# Sheet1.net
KiCad netlist of a schematic drawn in Altium Designer
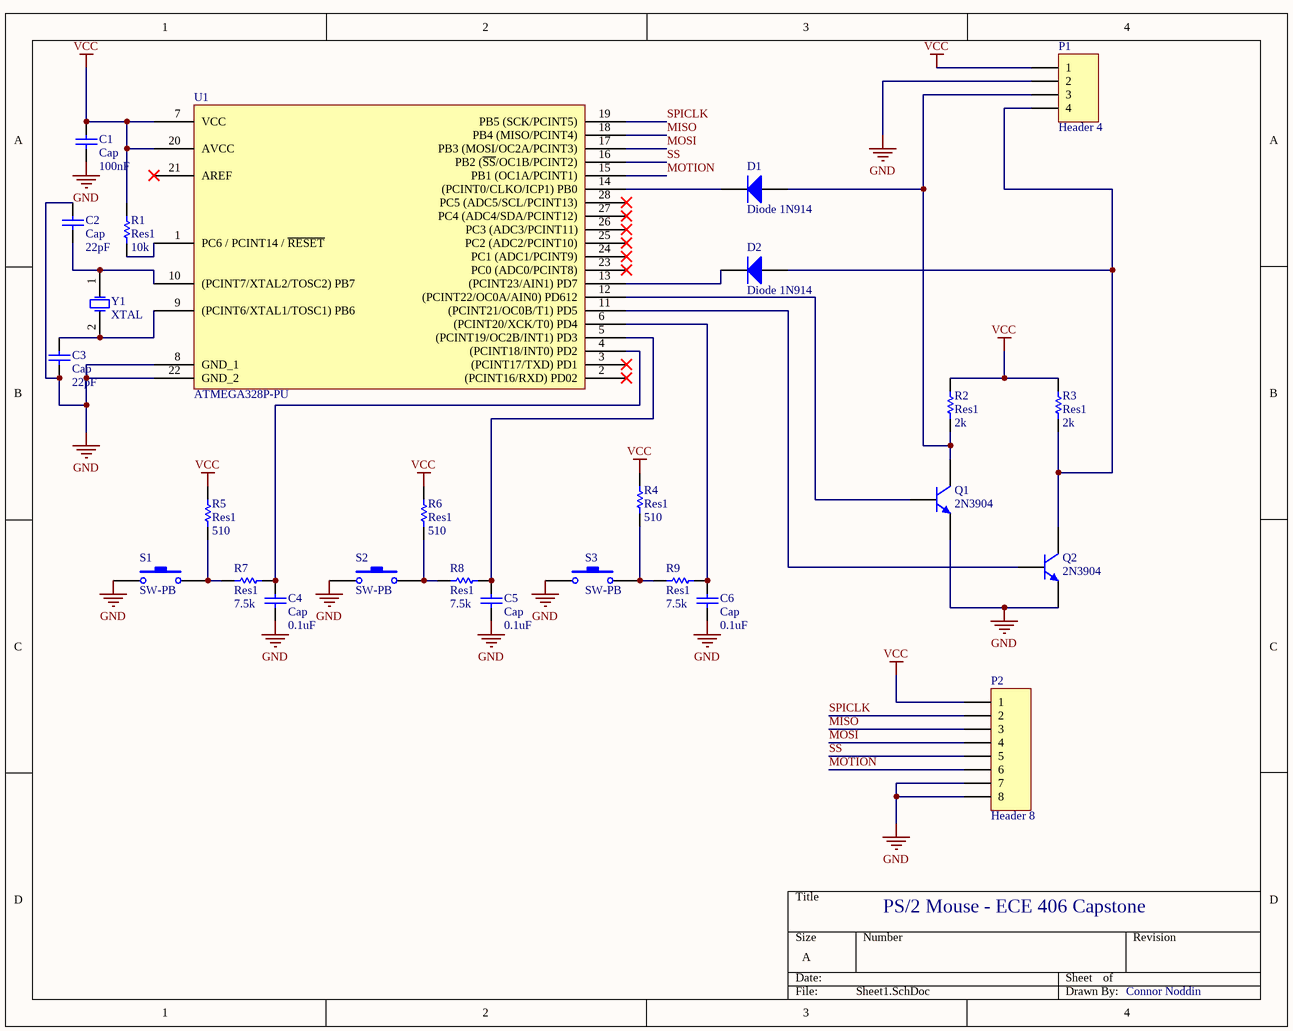
[diagram p0: Sheet1.SchDoc]

(export (version "E")
  (design (tool "Eeschema 10.0.6"))
  (components
    (comp (ref "C1")
      (value "Cap")
      (footprint "RAD-0.3")
      (description "Capacitor")
      (fields (field (name "ALTIUM_VALUE") "100nF") (field (name "PUBLISHER") "Altium Limited"))
      (libsource (lib "Miscellaneous Devices") (part "Cap"))
    )
    (comp (ref "C2")
      (value "Cap")
      (footprint "RAD-0.3")
      (description "Capacitor")
      (fields (field (name "ALTIUM_VALUE") "22pF") (field (name "PUBLISHER") "Altium Limited"))
      (libsource (lib "Miscellaneous Devices") (part "Cap"))
    )
    (comp (ref "C3")
      (value "Cap")
      (footprint "RAD-0.3")
      (description "Capacitor")
      (fields (field (name "ALTIUM_VALUE") "22pF") (field (name "PUBLISHER") "Altium Limited"))
      (libsource (lib "Miscellaneous Devices") (part "Cap"))
    )
    (comp (ref "C4")
      (value "Cap")
      (footprint "RAD-0.3")
      (description "Capacitor")
      (fields (field (name "ALTIUM_VALUE") "0.1uF") (field (name "PUBLISHER") "Altium Limited"))
      (libsource (lib "Miscellaneous Devices") (part "Cap"))
    )
    (comp (ref "C5")
      (value "Cap")
      (footprint "RAD-0.3")
      (description "Capacitor")
      (fields (field (name "ALTIUM_VALUE") "0.1uF") (field (name "PUBLISHER") "Altium Limited"))
      (libsource (lib "Miscellaneous Devices") (part "Cap"))
    )
    (comp (ref "C6")
      (value "Cap")
      (footprint "RAD-0.3")
      (description "Capacitor")
      (fields (field (name "ALTIUM_VALUE") "0.1uF") (field (name "PUBLISHER") "Altium Limited"))
      (libsource (lib "Miscellaneous Devices") (part "Cap"))
    )
    (comp (ref "D1")
      (value "Diode 1N914")
      (footprint "DO-35")
      (description "High Conductance Fast Diode")
      (fields (field (name "PUBLISHER") "Altium Limited"))
      (libsource (lib "Miscellaneous Devices") (part "Diode 1N914"))
    )
    (comp (ref "D2")
      (value "Diode 1N914")
      (footprint "DO-35")
      (description "High Conductance Fast Diode")
      (fields (field (name "PUBLISHER") "Altium Limited"))
      (libsource (lib "Miscellaneous Devices") (part "Diode 1N914"))
    )
    (comp (ref "P1")
      (value "Header 4")
      (footprint "HDR1X4")
      (description "Header, 4-Pin")
      (fields (field (name "PUBLISHER") "Altium Limited"))
      (libsource (lib "Miscellaneous Connectors") (part "Header 4"))
    )
    (comp (ref "P2")
      (value "Header 8")
      (footprint "HDR1X8")
      (description "Header, 8-Pin")
      (fields (field (name "PUBLISHER") "Altium Limited"))
      (libsource (lib "Miscellaneous Connectors") (part "Header 8"))
    )
    (comp (ref "Q1")
      (value "2N3904")
      (footprint "TO-92A")
      (description "NPN General Purpose Amplifier")
      (fields (field (name "PUBLISHER") "Altium Limited"))
      (libsource (lib "Miscellaneous Devices") (part "2N3904"))
    )
    (comp (ref "Q2")
      (value "2N3904")
      (footprint "TO-92A")
      (description "NPN General Purpose Amplifier")
      (fields (field (name "PUBLISHER") "Altium Limited"))
      (libsource (lib "Miscellaneous Devices") (part "2N3904"))
    )
    (comp (ref "R1")
      (value "Res1")
      (footprint "AXIAL-0.3")
      (description "Resistor")
      (fields (field (name "ALTIUM_VALUE") "10k") (field (name "PUBLISHER") "Altium Limited"))
      (libsource (lib "Miscellaneous Devices") (part "Res1"))
    )
    (comp (ref "R2")
      (value "Res1")
      (footprint "AXIAL-0.3")
      (description "Resistor")
      (fields (field (name "ALTIUM_VALUE") "2k") (field (name "PUBLISHER") "Altium Limited"))
      (libsource (lib "Miscellaneous Devices") (part "Res1"))
    )
    (comp (ref "R3")
      (value "Res1")
      (footprint "AXIAL-0.3")
      (description "Resistor")
      (fields (field (name "ALTIUM_VALUE") "2k") (field (name "PUBLISHER") "Altium Limited"))
      (libsource (lib "Miscellaneous Devices") (part "Res1"))
    )
    (comp (ref "R4")
      (value "Res1")
      (footprint "AXIAL-0.3")
      (description "Resistor")
      (fields (field (name "ALTIUM_VALUE") "510") (field (name "PUBLISHER") "Altium Limited"))
      (libsource (lib "Miscellaneous Devices") (part "Res1"))
    )
    (comp (ref "R5")
      (value "Res1")
      (footprint "AXIAL-0.3")
      (description "Resistor")
      (fields (field (name "ALTIUM_VALUE") "510") (field (name "PUBLISHER") "Altium Limited"))
      (libsource (lib "Miscellaneous Devices") (part "Res1"))
    )
    (comp (ref "R6")
      (value "Res1")
      (footprint "AXIAL-0.3")
      (description "Resistor")
      (fields (field (name "ALTIUM_VALUE") "510") (field (name "PUBLISHER") "Altium Limited"))
      (libsource (lib "Miscellaneous Devices") (part "Res1"))
    )
    (comp (ref "R7")
      (value "Res1")
      (footprint "AXIAL-0.3")
      (description "Resistor")
      (fields (field (name "ALTIUM_VALUE") "7.5k") (field (name "PUBLISHER") "Altium Limited"))
      (libsource (lib "Miscellaneous Devices") (part "Res1"))
    )
    (comp (ref "R8")
      (value "Res1")
      (footprint "AXIAL-0.3")
      (description "Resistor")
      (fields (field (name "ALTIUM_VALUE") "7.5k") (field (name "PUBLISHER") "Altium Limited"))
      (libsource (lib "Miscellaneous Devices") (part "Res1"))
    )
    (comp (ref "R9")
      (value "Res1")
      (footprint "AXIAL-0.3")
      (description "Resistor")
      (fields (field (name "ALTIUM_VALUE") "7.5k") (field (name "PUBLISHER") "Altium Limited"))
      (libsource (lib "Miscellaneous Devices") (part "Res1"))
    )
    (comp (ref "S1")
      (value "SW-PB")
      (footprint "SPST-2")
      (description "Switch")
      (fields (field (name "PUBLISHER") "Altium Limited"))
      (libsource (lib "Miscellaneous Devices") (part "SW-PB"))
    )
    (comp (ref "S2")
      (value "SW-PB")
      (footprint "SPST-2")
      (description "Switch")
      (fields (field (name "PUBLISHER") "Altium Limited"))
      (libsource (lib "Miscellaneous Devices") (part "SW-PB"))
    )
    (comp (ref "S3")
      (value "SW-PB")
      (footprint "SPST-2")
      (description "Switch")
      (fields (field (name "PUBLISHER") "Altium Limited"))
      (libsource (lib "Miscellaneous Devices") (part "SW-PB"))
    )
    (comp (ref "U1")
      (value "ATMEGA328P-PU")
      (footprint "27_DIP_7.62mm:27_DIP_7.62mm")
      (description "ATMEGA328P-PU; 8 bit Microcontroller AVR 20MHz 1; 32kb Flash; 2kb RAM; I2C SPI 2")
      (fields (field (name "MANUFACTURER") "Microchip / Atmel"))
      (libsource (lib "ATMEGA328P-PU") (part "ATMEGA328P-PU"))
    )
    (comp (ref "Y1")
      (value "XTAL")
      (footprint "R38")
      (description "Crystal Oscillator")
      (fields (field (name "PUBLISHER") "Altium Limited"))
      (libsource (lib "Miscellaneous Devices") (part "XTAL"))
    )
  )
  (nets
    (net (code "1") (name "/MISO") (class "Default")
      (node (ref "P2") (pin "3") (pinfunction "3_3") (pintype "passive"))
      (node (ref "U1") (pin "18") (pinfunction "PB4_(MISO/PCINT4)_18") (pintype "passive"))
    )
    (net (code "2") (name "/MOSI") (class "Default")
      (node (ref "P2") (pin "4") (pinfunction "4_4") (pintype "passive"))
      (node (ref "U1") (pin "17") (pinfunction "PB3_(MOSI/OC2A/PCINT3)_17") (pintype "passive"))
    )
    (net (code "3") (name "/MOTION") (class "Default")
      (node (ref "P2") (pin "6") (pinfunction "6_6") (pintype "passive"))
      (node (ref "U1") (pin "15") (pinfunction "PB1_(OC1A/PCINT1)_15") (pintype "passive"))
    )
    (net (code "4") (name "/SPICLK") (class "Default")
      (node (ref "P2") (pin "2") (pinfunction "2_2") (pintype "passive"))
      (node (ref "U1") (pin "19") (pinfunction "PB5_(SCK/PCINT5)_19") (pintype "passive"))
    )
    (net (code "5") (name "/SS") (class "Default")
      (node (ref "P2") (pin "5") (pinfunction "5_5") (pintype "passive"))
      (node (ref "U1") (pin "16") (pinfunction "PB2_(~{SS}/OC1B/PCINT2)_16") (pintype "passive"))
    )
    (net (code "6") (name "GND") (class "Default")
      (node (ref "C1") (pin "2") (pinfunction "2_2") (pintype "passive"))
      (node (ref "C2") (pin "1") (pinfunction "1_1") (pintype "passive"))
      (node (ref "C3") (pin "2") (pinfunction "2_2") (pintype "passive"))
      (node (ref "C4") (pin "1") (pinfunction "1_1") (pintype "passive"))
      (node (ref "C5") (pin "1") (pinfunction "1_1") (pintype "passive"))
      (node (ref "C6") (pin "1") (pinfunction "1_1") (pintype "passive"))
      (node (ref "P1") (pin "2") (pinfunction "2_2") (pintype "passive"))
      (node (ref "P2") (pin "7") (pinfunction "7_7") (pintype "passive"))
      (node (ref "P2") (pin "8") (pinfunction "8_8") (pintype "passive"))
      (node (ref "Q1") (pin "1") (pinfunction "E_1") (pintype "passive"))
      (node (ref "Q2") (pin "1") (pinfunction "E_1") (pintype "passive"))
      (node (ref "S1") (pin "1") (pinfunction "1_1") (pintype "passive"))
      (node (ref "S2") (pin "1") (pinfunction "1_1") (pintype "passive"))
      (node (ref "S3") (pin "1") (pinfunction "1_1") (pintype "passive"))
      (node (ref "U1") (pin "22") (pinfunction "GND_2_22") (pintype "passive"))
      (node (ref "U1") (pin "8") (pinfunction "GND_1_8") (pintype "passive"))
    )
    (net (code "7") (name "Net-(D1-A)") (class "Default")
      (node (ref "D1") (pin "1") (pinfunction "A_1") (pintype "passive"))
      (node (ref "P1") (pin "3") (pinfunction "3_3") (pintype "passive"))
      (node (ref "Q1") (pin "3") (pinfunction "C_3") (pintype "passive"))
      (node (ref "R2") (pin "1") (pinfunction "1_1") (pintype "passive"))
    )
    (net (code "8") (name "Net-(D1-K)") (class "Default")
      (node (ref "D1") (pin "2") (pinfunction "K_2") (pintype "passive"))
      (node (ref "U1") (pin "14") (pinfunction "(PCINT0/CLKO/ICP1)_PB0_14") (pintype "passive"))
    )
    (net (code "9") (name "Net-(D2-A)") (class "Default")
      (node (ref "D2") (pin "1") (pinfunction "A_1") (pintype "passive"))
      (node (ref "P1") (pin "4") (pinfunction "4_4") (pintype "passive"))
      (node (ref "Q2") (pin "3") (pinfunction "C_3") (pintype "passive"))
      (node (ref "R3") (pin "1") (pinfunction "1_1") (pintype "passive"))
    )
    (net (code "10") (name "Net-(D2-K)") (class "Default")
      (node (ref "D2") (pin "2") (pinfunction "K_2") (pintype "passive"))
      (node (ref "U1") (pin "13") (pinfunction "(PCINT23/AIN1)_PD7_13") (pintype "passive"))
    )
    (net (code "11") (name "Net-(Q1-B)") (class "Default")
      (node (ref "Q1") (pin "2") (pinfunction "B_2") (pintype "passive"))
      (node (ref "U1") (pin "12") (pinfunction "(PCINT22/OC0A/AIN0)_PD612_12") (pintype "passive"))
    )
    (net (code "12") (name "Net-(Q2-B)") (class "Default")
      (node (ref "Q2") (pin "2") (pinfunction "B_2") (pintype "passive"))
      (node (ref "U1") (pin "11") (pinfunction "(PCINT21/OC0B/T1)_PD5_11") (pintype "passive"))
    )
    (net (code "13") (name "Net-(R4-Pad1)") (class "Default")
      (node (ref "R4") (pin "1") (pinfunction "1_1") (pintype "passive"))
      (node (ref "R9") (pin "1") (pinfunction "1_1") (pintype "passive"))
      (node (ref "S3") (pin "2") (pinfunction "2_2") (pintype "passive"))
    )
    (net (code "14") (name "Net-(R5-Pad1)") (class "Default")
      (node (ref "R5") (pin "1") (pinfunction "1_1") (pintype "passive"))
      (node (ref "R7") (pin "1") (pinfunction "1_1") (pintype "passive"))
      (node (ref "S1") (pin "2") (pinfunction "2_2") (pintype "passive"))
    )
    (net (code "15") (name "Net-(R6-Pad1)") (class "Default")
      (node (ref "R6") (pin "1") (pinfunction "1_1") (pintype "passive"))
      (node (ref "R8") (pin "1") (pinfunction "1_1") (pintype "passive"))
      (node (ref "S2") (pin "2") (pinfunction "2_2") (pintype "passive"))
    )
    (net (code "16") (name "Net-(U1-(PCINT6{slash}XTAL1{slash}TOSC1)_PB6)") (class "Default")
      (node (ref "C3") (pin "1") (pinfunction "1_1") (pintype "passive"))
      (node (ref "U1") (pin "9") (pinfunction "(PCINT6/XTAL1/TOSC1)_PB6_9") (pintype "passive"))
      (node (ref "Y1") (pin "2") (pinfunction "OSC2_2") (pintype "passive"))
    )
    (net (code "17") (name "Net-(U1-(PCINT7{slash}XTAL2{slash}TOSC2)_PB7)") (class "Default")
      (node (ref "C2") (pin "2") (pinfunction "2_2") (pintype "passive"))
      (node (ref "U1") (pin "10") (pinfunction "(PCINT7/XTAL2/TOSC2)_PB7_10") (pintype "passive"))
      (node (ref "Y1") (pin "1") (pinfunction "OSC1_1") (pintype "passive"))
    )
    (net (code "18") (name "Net-(U1-(PCINT18{slash}INT0)_PD2)") (class "Default")
      (node (ref "C4") (pin "2") (pinfunction "2_2") (pintype "passive"))
      (node (ref "R7") (pin "2") (pinfunction "2_2") (pintype "passive"))
      (node (ref "U1") (pin "4") (pinfunction "(PCINT18/INT0)_PD2_4") (pintype "passive"))
    )
    (net (code "19") (name "Net-(U1-(PCINT19{slash}OC2B{slash}INT1)_PD3)") (class "Default")
      (node (ref "C5") (pin "2") (pinfunction "2_2") (pintype "passive"))
      (node (ref "R8") (pin "2") (pinfunction "2_2") (pintype "passive"))
      (node (ref "U1") (pin "5") (pinfunction "(PCINT19/OC2B/INT1)_PD3_5") (pintype "passive"))
    )
    (net (code "20") (name "Net-(U1-(PCINT20{slash}XCK{slash}T0)_PD4)") (class "Default")
      (node (ref "C6") (pin "2") (pinfunction "2_2") (pintype "passive"))
      (node (ref "R9") (pin "2") (pinfunction "2_2") (pintype "passive"))
      (node (ref "U1") (pin "6") (pinfunction "(PCINT20/XCK/T0)_PD4_6") (pintype "passive"))
    )
    (net (code "21") (name "Net-(U1-PC6_{slash}_PCINT14_{slash}_~{RESET})") (class "Default")
      (node (ref "R1") (pin "1") (pinfunction "1_1") (pintype "passive"))
      (node (ref "U1") (pin "1") (pinfunction "PC6_/_PCINT14_/_~{RESET}_1") (pintype "passive"))
    )
    (net (code "22") (name "VCC") (class "Default")
      (node (ref "C1") (pin "1") (pinfunction "1_1") (pintype "passive"))
      (node (ref "P1") (pin "1") (pinfunction "1_1") (pintype "passive"))
      (node (ref "P2") (pin "1") (pinfunction "1_1") (pintype "passive"))
      (node (ref "R1") (pin "2") (pinfunction "2_2") (pintype "passive"))
      (node (ref "R2") (pin "2") (pinfunction "2_2") (pintype "passive"))
      (node (ref "R3") (pin "2") (pinfunction "2_2") (pintype "passive"))
      (node (ref "R4") (pin "2") (pinfunction "2_2") (pintype "passive"))
      (node (ref "R5") (pin "2") (pinfunction "2_2") (pintype "passive"))
      (node (ref "R6") (pin "2") (pinfunction "2_2") (pintype "passive"))
      (node (ref "U1") (pin "20") (pinfunction "AVCC_20") (pintype "passive"))
      (node (ref "U1") (pin "7") (pinfunction "VCC_7") (pintype "passive"))
    )
    (net (code "23") (name "unconnected-(U1-(PCINT16{slash}RXD)_PD02-Pad2)") (class "Default")
      (node (ref "U1") (pin "2") (pinfunction "(PCINT16/RXD)_PD02_2") (pintype "passive+no_connect"))
    )
    (net (code "24") (name "unconnected-(U1-(PCINT17{slash}TXD)_PD1-Pad3)") (class "Default")
      (node (ref "U1") (pin "3") (pinfunction "(PCINT17/TXD)_PD1_3") (pintype "passive+no_connect"))
    )
    (net (code "25") (name "unconnected-(U1-AREF-Pad21)") (class "Default")
      (node (ref "U1") (pin "21") (pinfunction "AREF_21") (pintype "passive+no_connect"))
    )
    (net (code "26") (name "unconnected-(U1-PC0_(ADC0{slash}PCINT8)-Pad23)") (class "Default")
      (node (ref "U1") (pin "23") (pinfunction "PC0_(ADC0/PCINT8)_23") (pintype "passive+no_connect"))
    )
    (net (code "27") (name "unconnected-(U1-PC1_(ADC1{slash}PCINT9)-Pad24)") (class "Default")
      (node (ref "U1") (pin "24") (pinfunction "PC1_(ADC1/PCINT9)_24") (pintype "passive+no_connect"))
    )
    (net (code "28") (name "unconnected-(U1-PC2_(ADC2{slash}PCINT10)-Pad25)") (class "Default")
      (node (ref "U1") (pin "25") (pinfunction "PC2_(ADC2/PCINT10)_25") (pintype "passive+no_connect"))
    )
    (net (code "29") (name "unconnected-(U1-PC3_(ADC3{slash}PCINT11)-Pad26)") (class "Default")
      (node (ref "U1") (pin "26") (pinfunction "PC3_(ADC3/PCINT11)_26") (pintype "passive+no_connect"))
    )
    (net (code "30") (name "unconnected-(U1-PC4_(ADC4{slash}SDA{slash}PCINT12)-Pad27)") (class "Default")
      (node (ref "U1") (pin "27") (pinfunction "PC4_(ADC4/SDA/PCINT12)_27") (pintype "passive+no_connect"))
    )
    (net (code "31") (name "unconnected-(U1-PC5_(ADC5{slash}SCL{slash}PCINT13)-Pad28)") (class "Default")
      (node (ref "U1") (pin "28") (pinfunction "PC5_(ADC5/SCL/PCINT13)_28") (pintype "passive+no_connect"))
    )
  )
)
